# imp2_rev1.net
KiCad netlist of a schematic drawn in EAGLE
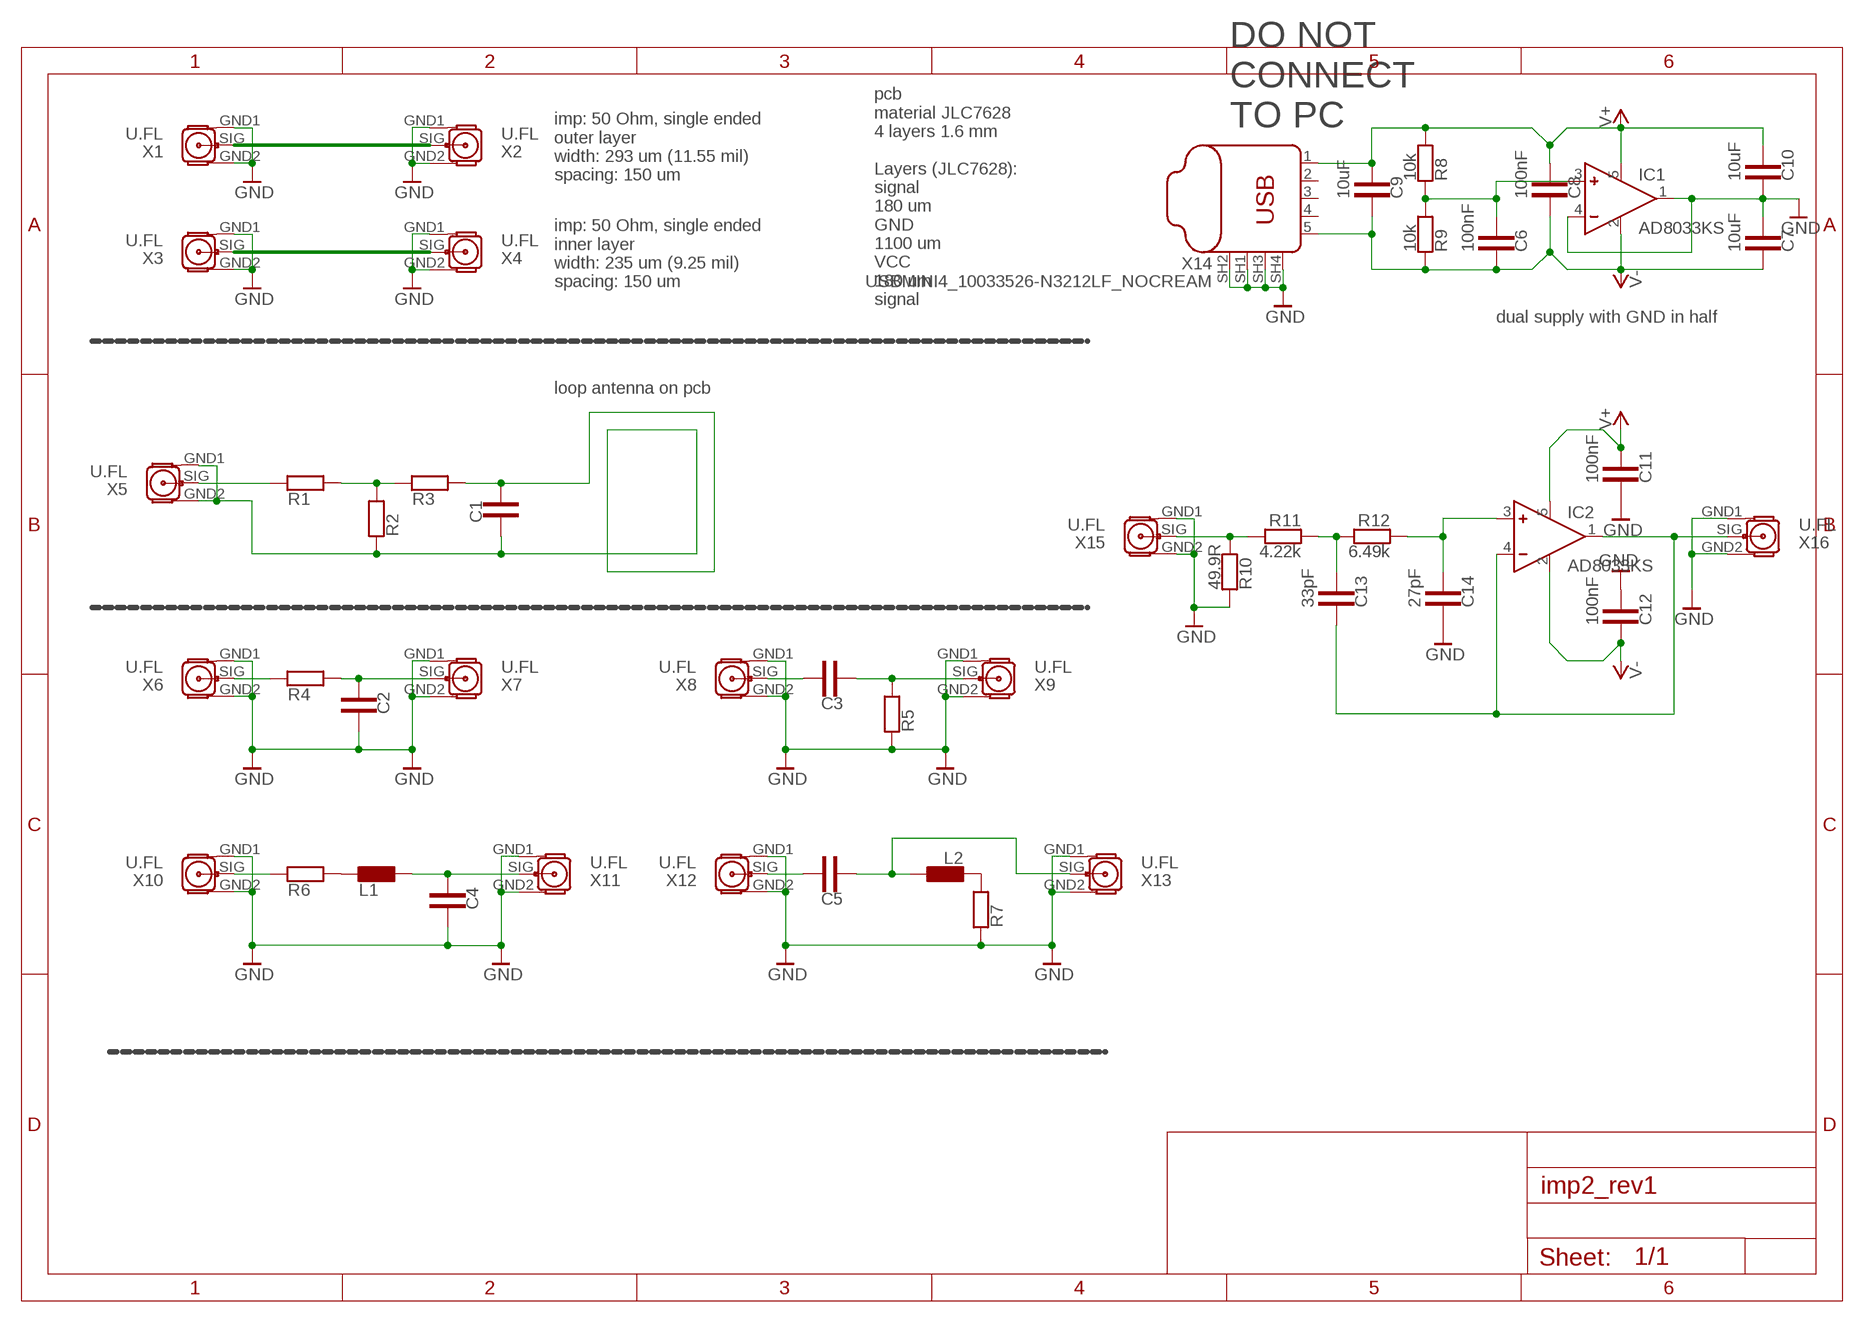
[diagram p0: schematic, sheet 1]

(export (version "E")
  (design (tool "Eeschema 10.0.6"))
  (components
    (comp (ref "C1")
      (value "C0603")
      (footprint "eagle-import:0603MIL")
      (libsource (lib "eagle-import") (part "C0603"))
    )
    (comp (ref "C2")
      (value "C0603")
      (footprint "eagle-import:0603MIL")
      (libsource (lib "eagle-import") (part "C0603"))
    )
    (comp (ref "C3")
      (value "C0603")
      (footprint "eagle-import:0603MIL")
      (libsource (lib "eagle-import") (part "C0603"))
    )
    (comp (ref "C4")
      (value "C0603")
      (footprint "eagle-import:0603MIL")
      (libsource (lib "eagle-import") (part "C0603"))
    )
    (comp (ref "C5")
      (value "C0603")
      (footprint "eagle-import:0603MIL")
      (libsource (lib "eagle-import") (part "C0603"))
    )
    (comp (ref "C6")
      (value "100nF")
      (footprint "eagle-import:0603MIL")
      (libsource (lib "eagle-import") (part "C0603"))
    )
    (comp (ref "C7")
      (value "10uF")
      (footprint "eagle-import:0805MIL")
      (libsource (lib "eagle-import") (part "C0805"))
    )
    (comp (ref "C8")
      (value "100nF")
      (footprint "eagle-import:0603MIL")
      (libsource (lib "eagle-import") (part "C0603"))
    )
    (comp (ref "C9")
      (value "10uF")
      (footprint "eagle-import:0805MIL")
      (libsource (lib "eagle-import") (part "C0805"))
    )
    (comp (ref "C10")
      (value "10uF")
      (footprint "eagle-import:0805MIL")
      (libsource (lib "eagle-import") (part "C0805"))
    )
    (comp (ref "C11")
      (value "100nF")
      (footprint "eagle-import:0603MIL")
      (libsource (lib "eagle-import") (part "C0603"))
    )
    (comp (ref "C12")
      (value "100nF")
      (footprint "eagle-import:0603MIL")
      (libsource (lib "eagle-import") (part "C0603"))
    )
    (comp (ref "C13")
      (value "33pF")
      (footprint "eagle-import:0603MIL")
      (libsource (lib "eagle-import") (part "C0603"))
    )
    (comp (ref "C14")
      (value "27pF")
      (footprint "eagle-import:0603MIL")
      (libsource (lib "eagle-import") (part "C0603"))
    )
    (comp (ref "IC1")
      (value "AD8033KS")
      (footprint "eagle-import:SC-705")
      (libsource (lib "eagle-import") (part "AD8033KS"))
    )
    (comp (ref "IC2")
      (value "AD8033KS")
      (footprint "eagle-import:SC-705")
      (libsource (lib "eagle-import") (part "AD8033KS"))
    )
    (comp (ref "L1")
      (value "L0603")
      (footprint "eagle-import:0603MIL")
      (libsource (lib "eagle-import") (part "L0603"))
    )
    (comp (ref "L2")
      (value "L0603")
      (footprint "eagle-import:0603MIL")
      (libsource (lib "eagle-import") (part "L0603"))
    )
    (comp (ref "R1")
      (value "R0603")
      (footprint "eagle-import:0603MIL")
      (libsource (lib "eagle-import") (part "R0603"))
    )
    (comp (ref "R2")
      (value "R0603")
      (footprint "eagle-import:0603MIL")
      (libsource (lib "eagle-import") (part "R0603"))
    )
    (comp (ref "R3")
      (value "R0603")
      (footprint "eagle-import:0603MIL")
      (libsource (lib "eagle-import") (part "R0603"))
    )
    (comp (ref "R4")
      (value "R0603")
      (footprint "eagle-import:0603MIL")
      (libsource (lib "eagle-import") (part "R0603"))
    )
    (comp (ref "R5")
      (value "R0603")
      (footprint "eagle-import:0603MIL")
      (libsource (lib "eagle-import") (part "R0603"))
    )
    (comp (ref "R6")
      (value "R0603")
      (footprint "eagle-import:0603MIL")
      (libsource (lib "eagle-import") (part "R0603"))
    )
    (comp (ref "R7")
      (value "R0603")
      (footprint "eagle-import:0603MIL")
      (libsource (lib "eagle-import") (part "R0603"))
    )
    (comp (ref "R8")
      (value "10k")
      (footprint "eagle-import:0603MIL")
      (libsource (lib "eagle-import") (part "R0603"))
    )
    (comp (ref "R9")
      (value "10k")
      (footprint "eagle-import:0603MIL")
      (libsource (lib "eagle-import") (part "R0603"))
    )
    (comp (ref "R10")
      (value "49.9R")
      (footprint "eagle-import:0603MIL")
      (libsource (lib "eagle-import") (part "R0603"))
    )
    (comp (ref "R11")
      (value "4.22k")
      (footprint "eagle-import:0603MIL")
      (libsource (lib "eagle-import") (part "R0603"))
    )
    (comp (ref "R12")
      (value "6.49k")
      (footprint "eagle-import:0603MIL")
      (libsource (lib "eagle-import") (part "R0603"))
    )
    (comp (ref "X1")
      (value "U.FL")
      (footprint "eagle-import:U.FL_CONUFL001-SMD")
      (libsource (lib "eagle-import") (part "U.FL"))
    )
    (comp (ref "X2")
      (value "U.FL")
      (footprint "eagle-import:U.FL_CONUFL001-SMD")
      (libsource (lib "eagle-import") (part "U.FL"))
    )
    (comp (ref "X3")
      (value "U.FL")
      (footprint "eagle-import:U.FL_CONUFL001-SMD")
      (libsource (lib "eagle-import") (part "U.FL"))
    )
    (comp (ref "X4")
      (value "U.FL")
      (footprint "eagle-import:U.FL_CONUFL001-SMD")
      (libsource (lib "eagle-import") (part "U.FL"))
    )
    (comp (ref "X5")
      (value "U.FL")
      (footprint "eagle-import:U.FL_CONUFL001-SMD")
      (libsource (lib "eagle-import") (part "U.FL"))
    )
    (comp (ref "X6")
      (value "U.FL")
      (footprint "eagle-import:U.FL_CONUFL001-SMD")
      (libsource (lib "eagle-import") (part "U.FL"))
    )
    (comp (ref "X7")
      (value "U.FL")
      (footprint "eagle-import:U.FL_CONUFL001-SMD")
      (libsource (lib "eagle-import") (part "U.FL"))
    )
    (comp (ref "X8")
      (value "U.FL")
      (footprint "eagle-import:U.FL_CONUFL001-SMD")
      (libsource (lib "eagle-import") (part "U.FL"))
    )
    (comp (ref "X9")
      (value "U.FL")
      (footprint "eagle-import:U.FL_CONUFL001-SMD")
      (libsource (lib "eagle-import") (part "U.FL"))
    )
    (comp (ref "X10")
      (value "U.FL")
      (footprint "eagle-import:U.FL_CONUFL001-SMD")
      (libsource (lib "eagle-import") (part "U.FL"))
    )
    (comp (ref "X11")
      (value "U.FL")
      (footprint "eagle-import:U.FL_CONUFL001-SMD")
      (libsource (lib "eagle-import") (part "U.FL"))
    )
    (comp (ref "X12")
      (value "U.FL")
      (footprint "eagle-import:U.FL_CONUFL001-SMD")
      (libsource (lib "eagle-import") (part "U.FL"))
    )
    (comp (ref "X13")
      (value "U.FL")
      (footprint "eagle-import:U.FL_CONUFL001-SMD")
      (libsource (lib "eagle-import") (part "U.FL"))
    )
    (comp (ref "X14")
      (value "USBMINI4_10033526-N3212LF_NOCREAM")
      (footprint "eagle-import:USB-MINI_SMD_10033526_NOCREAM")
      (libsource (lib "eagle-import") (part "USBMINI4_10033526-N3212LF_NOCREAM"))
    )
    (comp (ref "X15")
      (value "U.FL")
      (footprint "eagle-import:U.FL_CONUFL001-SMD")
      (libsource (lib "eagle-import") (part "U.FL"))
    )
    (comp (ref "X16")
      (value "U.FL")
      (footprint "eagle-import:U.FL_CONUFL001-SMD")
      (libsource (lib "eagle-import") (part "U.FL"))
    )
  )
  (nets
    (net (code "1") (name "GND") (class "Default")
      (node (ref "C10") (pin "1") (pinfunction "1_1") (pintype "passive"))
      (node (ref "C11") (pin "1") (pinfunction "1_1") (pintype "passive"))
      (node (ref "C12") (pin "2") (pinfunction "2_2") (pintype "passive"))
      (node (ref "C14") (pin "1") (pinfunction "1_1") (pintype "passive"))
      (node (ref "C2") (pin "1") (pinfunction "1_1") (pintype "passive"))
      (node (ref "C4") (pin "1") (pinfunction "1_1") (pintype "passive"))
      (node (ref "C7") (pin "2") (pinfunction "2_2") (pintype "passive"))
      (node (ref "IC1") (pin "1") (pinfunction "OUT_1") (pintype "bidirectional"))
      (node (ref "IC1") (pin "4") (pinfunction "IN-_4") (pintype "bidirectional"))
      (node (ref "R10") (pin "1") (pinfunction "1_1") (pintype "passive"))
      (node (ref "R5") (pin "1") (pinfunction "1_1") (pintype "passive"))
      (node (ref "R7") (pin "1") (pinfunction "1_1") (pintype "passive"))
      (node (ref "X1") (pin "GND1") (pinfunction "GND1_GND1") (pintype "bidirectional"))
      (node (ref "X1") (pin "GND2") (pinfunction "GND2_GND2") (pintype "bidirectional"))
      (node (ref "X10") (pin "GND1") (pinfunction "GND1_GND1") (pintype "bidirectional"))
      (node (ref "X10") (pin "GND2") (pinfunction "GND2_GND2") (pintype "bidirectional"))
      (node (ref "X11") (pin "GND1") (pinfunction "GND1_GND1") (pintype "bidirectional"))
      (node (ref "X11") (pin "GND2") (pinfunction "GND2_GND2") (pintype "bidirectional"))
      (node (ref "X12") (pin "GND1") (pinfunction "GND1_GND1") (pintype "bidirectional"))
      (node (ref "X12") (pin "GND2") (pinfunction "GND2_GND2") (pintype "bidirectional"))
      (node (ref "X13") (pin "GND1") (pinfunction "GND1_GND1") (pintype "bidirectional"))
      (node (ref "X13") (pin "GND2") (pinfunction "GND2_GND2") (pintype "bidirectional"))
      (node (ref "X14") (pin "SH1") (pinfunction "G1_SH1") (pintype "bidirectional"))
      (node (ref "X14") (pin "SH2") (pinfunction "G2_SH2") (pintype "bidirectional"))
      (node (ref "X14") (pin "SH3") (pinfunction "G3_SH3") (pintype "bidirectional"))
      (node (ref "X14") (pin "SH4") (pinfunction "G4_SH4") (pintype "bidirectional"))
      (node (ref "X15") (pin "GND1") (pinfunction "GND1_GND1") (pintype "bidirectional"))
      (node (ref "X15") (pin "GND2") (pinfunction "GND2_GND2") (pintype "bidirectional"))
      (node (ref "X16") (pin "GND1") (pinfunction "GND1_GND1") (pintype "bidirectional"))
      (node (ref "X16") (pin "GND2") (pinfunction "GND2_GND2") (pintype "bidirectional"))
      (node (ref "X2") (pin "GND1") (pinfunction "GND1_GND1") (pintype "bidirectional"))
      (node (ref "X2") (pin "GND2") (pinfunction "GND2_GND2") (pintype "bidirectional"))
      (node (ref "X3") (pin "GND1") (pinfunction "GND1_GND1") (pintype "bidirectional"))
      (node (ref "X3") (pin "GND2") (pinfunction "GND2_GND2") (pintype "bidirectional"))
      (node (ref "X4") (pin "GND1") (pinfunction "GND1_GND1") (pintype "bidirectional"))
      (node (ref "X4") (pin "GND2") (pinfunction "GND2_GND2") (pintype "bidirectional"))
      (node (ref "X6") (pin "GND1") (pinfunction "GND1_GND1") (pintype "bidirectional"))
      (node (ref "X6") (pin "GND2") (pinfunction "GND2_GND2") (pintype "bidirectional"))
      (node (ref "X7") (pin "GND1") (pinfunction "GND1_GND1") (pintype "bidirectional"))
      (node (ref "X7") (pin "GND2") (pinfunction "GND2_GND2") (pintype "bidirectional"))
      (node (ref "X8") (pin "GND1") (pinfunction "GND1_GND1") (pintype "bidirectional"))
      (node (ref "X8") (pin "GND2") (pinfunction "GND2_GND2") (pintype "bidirectional"))
      (node (ref "X9") (pin "GND1") (pinfunction "GND1_GND1") (pintype "bidirectional"))
      (node (ref "X9") (pin "GND2") (pinfunction "GND2_GND2") (pintype "bidirectional"))
    )
    (net (code "2") (name "Net-(C1-Pad1)") (class "Default")
      (node (ref "C1") (pin "1") (pinfunction "1_1") (pintype "passive"))
      (node (ref "C1") (pin "2") (pinfunction "2_2") (pintype "passive"))
      (node (ref "R2") (pin "1") (pinfunction "1_1") (pintype "passive"))
      (node (ref "R3") (pin "2") (pinfunction "2_2") (pintype "passive"))
      (node (ref "X5") (pin "GND1") (pinfunction "GND1_GND1") (pintype "bidirectional"))
      (node (ref "X5") (pin "GND2") (pinfunction "GND2_GND2") (pintype "bidirectional"))
    )
    (net (code "3") (name "Net-(C2-Pad2)") (class "Default")
      (node (ref "C2") (pin "2") (pinfunction "2_2") (pintype "passive"))
      (node (ref "R4") (pin "2") (pinfunction "2_2") (pintype "passive"))
      (node (ref "X7") (pin "SIG") (pinfunction "SIG_SIG") (pintype "bidirectional"))
    )
    (net (code "4") (name "Net-(C3-Pad1)") (class "Default")
      (node (ref "C3") (pin "1") (pinfunction "1_1") (pintype "passive"))
      (node (ref "X8") (pin "SIG") (pinfunction "SIG_SIG") (pintype "bidirectional"))
    )
    (net (code "5") (name "Net-(C3-Pad2)") (class "Default")
      (node (ref "C3") (pin "2") (pinfunction "2_2") (pintype "passive"))
      (node (ref "R5") (pin "2") (pinfunction "2_2") (pintype "passive"))
      (node (ref "X9") (pin "SIG") (pinfunction "SIG_SIG") (pintype "bidirectional"))
    )
    (net (code "6") (name "Net-(C4-Pad2)") (class "Default")
      (node (ref "C4") (pin "2") (pinfunction "2_2") (pintype "passive"))
      (node (ref "L1") (pin "2") (pinfunction "2_2") (pintype "passive"))
      (node (ref "X11") (pin "SIG") (pinfunction "SIG_SIG") (pintype "bidirectional"))
    )
    (net (code "7") (name "Net-(C5-Pad1)") (class "Default")
      (node (ref "C5") (pin "1") (pinfunction "1_1") (pintype "passive"))
      (node (ref "X12") (pin "SIG") (pinfunction "SIG_SIG") (pintype "bidirectional"))
    )
    (net (code "8") (name "Net-(C5-Pad2)") (class "Default")
      (node (ref "C5") (pin "2") (pinfunction "2_2") (pintype "passive"))
      (node (ref "L2") (pin "2") (pinfunction "2_2") (pintype "passive"))
      (node (ref "X13") (pin "SIG") (pinfunction "SIG_SIG") (pintype "bidirectional"))
    )
    (net (code "9") (name "Net-(C13-Pad2)") (class "Default")
      (node (ref "C13") (pin "2") (pinfunction "2_2") (pintype "passive"))
      (node (ref "R11") (pin "1") (pinfunction "1_1") (pintype "passive"))
      (node (ref "R12") (pin "2") (pinfunction "2_2") (pintype "passive"))
    )
    (net (code "10") (name "Net-(IC1-IN+)") (class "Default")
      (node (ref "C6") (pin "2") (pinfunction "2_2") (pintype "passive"))
      (node (ref "IC1") (pin "3") (pinfunction "IN+_3") (pintype "bidirectional"))
      (node (ref "R8") (pin "1") (pinfunction "1_1") (pintype "passive"))
      (node (ref "R9") (pin "2") (pinfunction "2_2") (pintype "passive"))
    )
    (net (code "11") (name "Net-(IC2-IN+)") (class "Default")
      (node (ref "C14") (pin "2") (pinfunction "2_2") (pintype "passive"))
      (node (ref "IC2") (pin "3") (pinfunction "IN+_3") (pintype "bidirectional"))
      (node (ref "R12") (pin "1") (pinfunction "1_1") (pintype "passive"))
    )
    (net (code "12") (name "Net-(IC2-IN-)") (class "Default")
      (node (ref "C13") (pin "1") (pinfunction "1_1") (pintype "passive"))
      (node (ref "IC2") (pin "1") (pinfunction "OUT_1") (pintype "bidirectional"))
      (node (ref "IC2") (pin "4") (pinfunction "IN-_4") (pintype "bidirectional"))
      (node (ref "X16") (pin "SIG") (pinfunction "SIG_SIG") (pintype "bidirectional"))
    )
    (net (code "13") (name "Net-(L1-Pad1)") (class "Default")
      (node (ref "L1") (pin "1") (pinfunction "1_1") (pintype "passive"))
      (node (ref "R6") (pin "2") (pinfunction "2_2") (pintype "passive"))
    )
    (net (code "14") (name "Net-(L2-Pad1)") (class "Default")
      (node (ref "L2") (pin "1") (pinfunction "1_1") (pintype "passive"))
      (node (ref "R7") (pin "2") (pinfunction "2_2") (pintype "passive"))
    )
    (net (code "15") (name "Net-(R1-Pad1)") (class "Default")
      (node (ref "R1") (pin "1") (pinfunction "1_1") (pintype "passive"))
      (node (ref "X5") (pin "SIG") (pinfunction "SIG_SIG") (pintype "bidirectional"))
    )
    (net (code "16") (name "Net-(R1-Pad2)") (class "Default")
      (node (ref "R1") (pin "2") (pinfunction "2_2") (pintype "passive"))
      (node (ref "R2") (pin "2") (pinfunction "2_2") (pintype "passive"))
      (node (ref "R3") (pin "1") (pinfunction "1_1") (pintype "passive"))
    )
    (net (code "17") (name "Net-(R4-Pad1)") (class "Default")
      (node (ref "R4") (pin "1") (pinfunction "1_1") (pintype "passive"))
      (node (ref "X6") (pin "SIG") (pinfunction "SIG_SIG") (pintype "bidirectional"))
    )
    (net (code "18") (name "Net-(R6-Pad1)") (class "Default")
      (node (ref "R6") (pin "1") (pinfunction "1_1") (pintype "passive"))
      (node (ref "X10") (pin "SIG") (pinfunction "SIG_SIG") (pintype "bidirectional"))
    )
    (net (code "19") (name "Net-(R10-Pad2)") (class "Default")
      (node (ref "R10") (pin "2") (pinfunction "2_2") (pintype "passive"))
      (node (ref "R11") (pin "2") (pinfunction "2_2") (pintype "passive"))
      (node (ref "X15") (pin "SIG") (pinfunction "SIG_SIG") (pintype "bidirectional"))
    )
    (net (code "20") (name "Net-(X1-PadSIG)") (class "Default")
      (node (ref "X1") (pin "SIG") (pinfunction "SIG_SIG") (pintype "bidirectional"))
      (node (ref "X2") (pin "SIG") (pinfunction "SIG_SIG") (pintype "bidirectional"))
    )
    (net (code "21") (name "Net-(X3-PadSIG)") (class "Default")
      (node (ref "X3") (pin "SIG") (pinfunction "SIG_SIG") (pintype "bidirectional"))
      (node (ref "X4") (pin "SIG") (pinfunction "SIG_SIG") (pintype "bidirectional"))
    )
    (net (code "22") (name "V+") (class "Default")
      (node (ref "C10") (pin "2") (pinfunction "2_2") (pintype "passive"))
      (node (ref "C11") (pin "2") (pinfunction "2_2") (pintype "passive"))
      (node (ref "C8") (pin "2") (pinfunction "2_2") (pintype "passive"))
      (node (ref "C9") (pin "2") (pinfunction "2_2") (pintype "passive"))
      (node (ref "IC1") (pin "5") (pinfunction "VDD_5") (pintype "bidirectional"))
      (node (ref "IC2") (pin "5") (pinfunction "VDD_5") (pintype "bidirectional"))
      (node (ref "R8") (pin "2") (pinfunction "2_2") (pintype "passive"))
      (node (ref "X14") (pin "1") (pinfunction "VBUS_1") (pintype "bidirectional"))
    )
    (net (code "23") (name "V-") (class "Default")
      (node (ref "C12") (pin "1") (pinfunction "1_1") (pintype "passive"))
      (node (ref "C6") (pin "1") (pinfunction "1_1") (pintype "passive"))
      (node (ref "C7") (pin "1") (pinfunction "1_1") (pintype "passive"))
      (node (ref "C8") (pin "1") (pinfunction "1_1") (pintype "passive"))
      (node (ref "C9") (pin "1") (pinfunction "1_1") (pintype "passive"))
      (node (ref "IC1") (pin "2") (pinfunction "VSS_2") (pintype "bidirectional"))
      (node (ref "IC2") (pin "2") (pinfunction "VSS_2") (pintype "bidirectional"))
      (node (ref "R9") (pin "1") (pinfunction "1_1") (pintype "passive"))
      (node (ref "X14") (pin "5") (pinfunction "GND_5") (pintype "bidirectional"))
    )
    (net (code "24") (name "unconnected-(X14-D+-Pad3)") (class "Default")
      (node (ref "X14") (pin "3") (pinfunction "D+_3") (pintype "bidirectional"))
    )
    (net (code "25") (name "unconnected-(X14-D--Pad2)") (class "Default")
      (node (ref "X14") (pin "2") (pinfunction "D-_2") (pintype "bidirectional"))
    )
    (net (code "26") (name "unconnected-(X14-ID-Pad4)") (class "Default")
      (node (ref "X14") (pin "4") (pinfunction "ID_4") (pintype "bidirectional"))
    )
  )
)
